# SeanOptoIsolatorCircuit.net
KiCad netlist of a schematic drawn in EAGLE
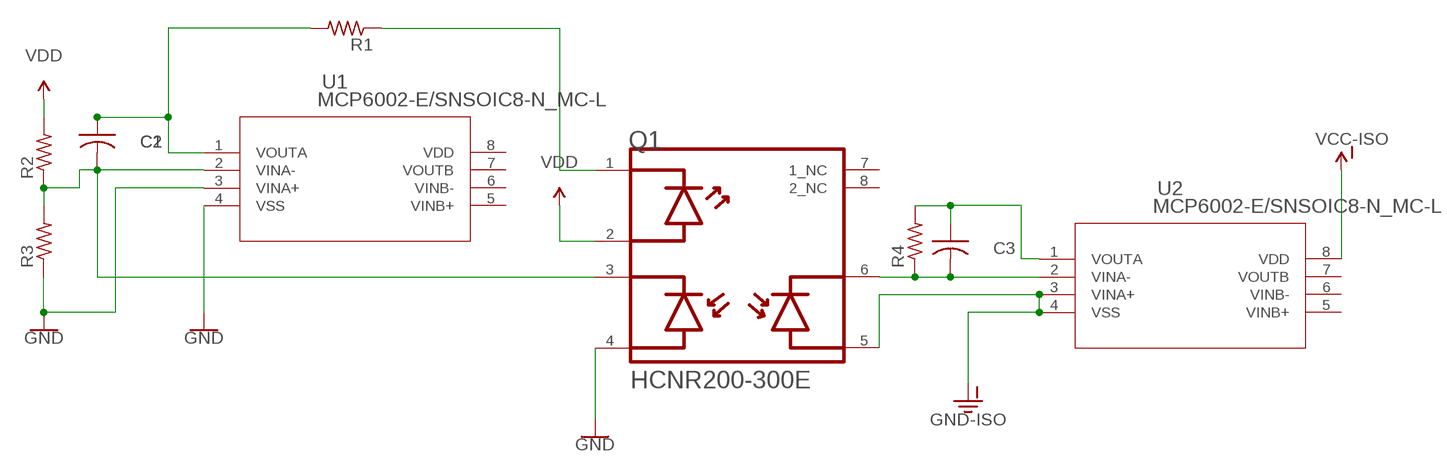
[diagram p0: schematic, sheet 1]

(export (version "E")
  (design (tool "Eeschema 10.0.6"))
  (components
    (comp (ref "C1")
      (value "C-US025-024X044")
      (footprint "eagle-import:C025-024X044")
      (libsource (lib "eagle-import") (part "C-US025-024X044"))
    )
    (comp (ref "C2")
      (value "C-US025-024X044")
      (footprint "eagle-import:C025-024X044")
      (libsource (lib "eagle-import") (part "C-US025-024X044"))
    )
    (comp (ref "C3")
      (value "C-US025-024X044")
      (footprint "eagle-import:C025-024X044")
      (libsource (lib "eagle-import") (part "C-US025-024X044"))
    )
    (comp (ref "Q1")
      (value "BROADCOM_HCNR200-300EBROADCOM_HCNR200-300E_0_0")
      (footprint "eagle-import:BROADCOM_HCNR200-300E_0")
      (fields
        (field (name "DIGIKEY_PART_NUMBER") "516-1608-5-ND")
        (field (name "MF") "Broadcom")
        (field (name "MOUSER_PART_NUMBER") "630-HCNR200-300E")
      )
      (libsource (lib "eagle-import") (part "BROADCOM_HCNR200-300EBROADCOM_HCNR200-300E_0_0"))
    )
    (comp (ref "R1")
      (value "R-US_0204/5")
      (footprint "eagle-import:0204_5")
      (libsource (lib "eagle-import") (part "R-US_0204/5"))
    )
    (comp (ref "R2")
      (value "R-US_0204/5")
      (footprint "eagle-import:0204_5")
      (libsource (lib "eagle-import") (part "R-US_0204/5"))
    )
    (comp (ref "R3")
      (value "R-US_0204/5")
      (footprint "eagle-import:0204_5")
      (libsource (lib "eagle-import") (part "R-US_0204/5"))
    )
    (comp (ref "R4")
      (value "R-US_0204/5")
      (footprint "eagle-import:0204_5")
      (libsource (lib "eagle-import") (part "R-US_0204/5"))
    )
    (comp (ref "U1")
      (value "MCP6002-E/SNSOIC8-N_MC-L")
      (footprint "eagle-import:SOIC8-N_MC-L")
      (fields
        (field (name "MANUFACTURER_PART_NUMBER") "MCP6002-E/SN")
        (field (name "COPYRIGHT") "Copyright (C) 2018 Accelerated Designs. All rights reserved")
      )
      (libsource (lib "eagle-import") (part "MCP6002-E/SNSOIC8-N_MC-L"))
    )
    (comp (ref "U2")
      (value "MCP6002-E/SNSOIC8-N_MC-L")
      (footprint "eagle-import:SOIC8-N_MC-L")
      (fields
        (field (name "MANUFACTURER_PART_NUMBER") "MCP6002-E/SN")
        (field (name "COPYRIGHT") "Copyright (C) 2018 Accelerated Designs. All rights reserved")
      )
      (libsource (lib "eagle-import") (part "MCP6002-E/SNSOIC8-N_MC-L"))
    )
  )
  (nets
    (net (code "1") (name "GND") (class "Default")
      (node (ref "Q1") (pin "4") (pinfunction "PD1_ANODE_4") (pintype "passive"))
      (node (ref "R3") (pin "1") (pinfunction "1_1") (pintype "passive"))
      (node (ref "U1") (pin "3") (pinfunction "VINA+_3") (pintype "passive"))
      (node (ref "U1") (pin "4") (pinfunction "VSS_4") (pintype "passive"))
    )
    (net (code "2") (name "GND-ISO") (class "Default")
      (node (ref "Q1") (pin "5") (pinfunction "PD2_ANODE_5") (pintype "passive"))
      (node (ref "U2") (pin "3") (pinfunction "VINA+_3") (pintype "passive"))
      (node (ref "U2") (pin "4") (pinfunction "VSS_4") (pintype "passive"))
    )
    (net (code "3") (name "Net-(Q1-LED_CATHODE)") (class "Default")
      (node (ref "Q1") (pin "1") (pinfunction "LED_CATHODE_1") (pintype "passive"))
      (node (ref "R1") (pin "1") (pinfunction "1_1") (pintype "passive"))
    )
    (net (code "4") (name "Net-(Q1-PD1_CATHODE)") (class "Default")
      (node (ref "C1") (pin "2") (pinfunction "2_2") (pintype "passive"))
      (node (ref "C2") (pin "2") (pinfunction "2_2") (pintype "passive"))
      (node (ref "Q1") (pin "3") (pinfunction "PD1_CATHODE_3") (pintype "passive"))
      (node (ref "R2") (pin "1") (pinfunction "1_1") (pintype "passive"))
      (node (ref "R3") (pin "2") (pinfunction "2_2") (pintype "passive"))
      (node (ref "U1") (pin "2") (pinfunction "VINA-_2") (pintype "passive"))
    )
    (net (code "5") (name "Net-(Q1-PD2_CATHODE)") (class "Default")
      (node (ref "C3") (pin "2") (pinfunction "2_2") (pintype "passive"))
      (node (ref "Q1") (pin "6") (pinfunction "PD2_CATHODE_6") (pintype "passive"))
      (node (ref "R4") (pin "1") (pinfunction "1_1") (pintype "passive"))
      (node (ref "U2") (pin "2") (pinfunction "VINA-_2") (pintype "passive"))
    )
    (net (code "6") (name "Net-(U1-VOUTA)") (class "Default")
      (node (ref "C1") (pin "1") (pinfunction "1_1") (pintype "passive"))
      (node (ref "C2") (pin "1") (pinfunction "1_1") (pintype "passive"))
      (node (ref "R1") (pin "2") (pinfunction "2_2") (pintype "passive"))
      (node (ref "U1") (pin "1") (pinfunction "VOUTA_1") (pintype "passive"))
    )
    (net (code "7") (name "Net-(U2-VOUTA)") (class "Default")
      (node (ref "C3") (pin "1") (pinfunction "1_1") (pintype "passive"))
      (node (ref "R4") (pin "2") (pinfunction "2_2") (pintype "passive"))
      (node (ref "U2") (pin "1") (pinfunction "VOUTA_1") (pintype "passive"))
    )
    (net (code "8") (name "VCC-ISO") (class "Default")
      (node (ref "U2") (pin "8") (pinfunction "VDD_8") (pintype "passive"))
    )
    (net (code "9") (name "VDD") (class "Default")
      (node (ref "Q1") (pin "2") (pinfunction "LED_ANODE_2") (pintype "passive"))
      (node (ref "R2") (pin "2") (pinfunction "2_2") (pintype "passive"))
    )
    (net (code "10") (name "unconnected-(Q1-1_NC-Pad7)") (class "Default")
      (node (ref "Q1") (pin "7") (pinfunction "1_NC_7") (pintype "passive"))
    )
    (net (code "11") (name "unconnected-(Q1-2_NC-Pad8)") (class "Default")
      (node (ref "Q1") (pin "8") (pinfunction "2_NC_8") (pintype "passive"))
    )
    (net (code "12") (name "unconnected-(U1-VDD-Pad8)") (class "Default")
      (node (ref "U1") (pin "8") (pinfunction "VDD_8") (pintype "passive"))
    )
    (net (code "13") (name "unconnected-(U1-VINB+-Pad5)") (class "Default")
      (node (ref "U1") (pin "5") (pinfunction "VINB+_5") (pintype "passive"))
    )
    (net (code "14") (name "unconnected-(U1-VINB--Pad6)") (class "Default")
      (node (ref "U1") (pin "6") (pinfunction "VINB-_6") (pintype "passive"))
    )
    (net (code "15") (name "unconnected-(U1-VOUTB-Pad7)") (class "Default")
      (node (ref "U1") (pin "7") (pinfunction "VOUTB_7") (pintype "passive"))
    )
    (net (code "16") (name "unconnected-(U2-VINB+-Pad5)") (class "Default")
      (node (ref "U2") (pin "5") (pinfunction "VINB+_5") (pintype "passive"))
    )
    (net (code "17") (name "unconnected-(U2-VINB--Pad6)") (class "Default")
      (node (ref "U2") (pin "6") (pinfunction "VINB-_6") (pintype "passive"))
    )
    (net (code "18") (name "unconnected-(U2-VOUTB-Pad7)") (class "Default")
      (node (ref "U2") (pin "7") (pinfunction "VOUTB_7") (pintype "passive"))
    )
  )
)
